# haasoscope_trigger_board_v1_1.net
KiCad netlist of a schematic drawn in EAGLE
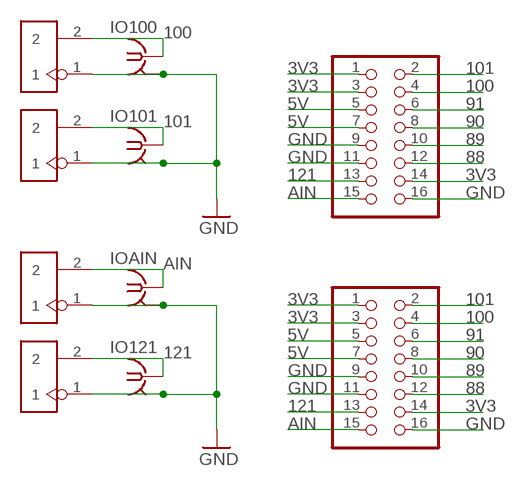
[diagram p0: schematic, sheet 1]

(export (version "E")
  (design (tool "Eeschema 10.0.6"))
  (components
    (comp (ref "IO100")
      (value "BU-SMB-V")
      (footprint "eagle-import:BU-SMB-V")
      (libsource (lib "eagle-import") (part "BU-SMB-V"))
    )
    (comp (ref "IO101")
      (value "BU-SMB-V")
      (footprint "eagle-import:BU-SMB-V")
      (libsource (lib "eagle-import") (part "BU-SMB-V"))
    )
    (comp (ref "IO121")
      (value "BU-SMB-V")
      (footprint "eagle-import:BU-SMB-V")
      (libsource (lib "eagle-import") (part "BU-SMB-V"))
    )
    (comp (ref "IOAIN")
      (value "BU-SMB-V")
      (footprint "eagle-import:BU-SMB-V")
      (libsource (lib "eagle-import") (part "BU-SMB-V"))
    )
    (comp (ref "J1")
      (value "2p-2.54")
      (footprint "eagle-import:H2-2.54")
      (fields (field (name "MPN") "P125-1102A0BS116A1"))
      (libsource (lib "eagle-import") (part "DIP-BLACK-MALE-HEADER-VERT(2P-2.54)"))
    )
    (comp (ref "J2")
      (value "2p-2.54")
      (footprint "eagle-import:H2-2.54")
      (fields (field (name "MPN") "P125-1102A0BS116A1"))
      (libsource (lib "eagle-import") (part "DIP-BLACK-MALE-HEADER-VERT(2P-2.54)"))
    )
    (comp (ref "J3")
      (value "2p-2.54")
      (footprint "eagle-import:H2-2.54")
      (fields (field (name "MPN") "P125-1102A0BS116A1"))
      (libsource (lib "eagle-import") (part "DIP-BLACK-MALE-HEADER-VERT(2P-2.54)"))
    )
    (comp (ref "J4")
      (value "2p-2.54")
      (footprint "eagle-import:H2-2.54")
      (fields (field (name "MPN") "P125-1102A0BS116A1"))
      (libsource (lib "eagle-import") (part "DIP-BLACK-MALE-HEADER-VERT(2P-2.54)"))
    )
    (comp (ref "JP1")
      (value "Jp1")
      (footprint "eagle-import:2X08")
      (libsource (lib "eagle-import") (part "PINHD-2X8"))
    )
    (comp (ref "JP2")
      (value "JP2")
      (footprint "eagle-import:2X08")
      (libsource (lib "eagle-import") (part "PINHD-2X8"))
    )
  )
  (nets
    (net (code "1") (name "/3V3") (class "Default")
      (node (ref "JP1") (pin "1") (pinfunction "1_1") (pintype "passive"))
      (node (ref "JP1") (pin "14") (pinfunction "14_14") (pintype "passive"))
      (node (ref "JP1") (pin "3") (pinfunction "3_3") (pintype "passive"))
      (node (ref "JP2") (pin "1") (pinfunction "1_1") (pintype "passive"))
      (node (ref "JP2") (pin "14") (pinfunction "14_14") (pintype "passive"))
      (node (ref "JP2") (pin "3") (pinfunction "3_3") (pintype "passive"))
    )
    (net (code "2") (name "/5V") (class "Default")
      (node (ref "JP1") (pin "5") (pinfunction "5_5") (pintype "passive"))
      (node (ref "JP1") (pin "7") (pinfunction "7_7") (pintype "passive"))
      (node (ref "JP2") (pin "5") (pinfunction "5_5") (pintype "passive"))
      (node (ref "JP2") (pin "7") (pinfunction "7_7") (pintype "passive"))
    )
    (net (code "3") (name "/88") (class "Default")
      (node (ref "JP1") (pin "12") (pinfunction "12_12") (pintype "passive"))
      (node (ref "JP2") (pin "12") (pinfunction "12_12") (pintype "passive"))
    )
    (net (code "4") (name "/89") (class "Default")
      (node (ref "JP1") (pin "10") (pinfunction "10_10") (pintype "passive"))
      (node (ref "JP2") (pin "10") (pinfunction "10_10") (pintype "passive"))
    )
    (net (code "5") (name "/90") (class "Default")
      (node (ref "JP1") (pin "8") (pinfunction "8_8") (pintype "passive"))
      (node (ref "JP2") (pin "8") (pinfunction "8_8") (pintype "passive"))
    )
    (net (code "6") (name "/91") (class "Default")
      (node (ref "JP1") (pin "6") (pinfunction "6_6") (pintype "passive"))
      (node (ref "JP2") (pin "6") (pinfunction "6_6") (pintype "passive"))
    )
    (net (code "7") (name "/100") (class "Default")
      (node (ref "IO100") (pin "1") (pinfunction "1_1") (pintype "passive"))
      (node (ref "J1") (pin "2") (pinfunction "2_2") (pintype "bidirectional"))
      (node (ref "JP1") (pin "4") (pinfunction "4_4") (pintype "passive"))
      (node (ref "JP2") (pin "4") (pinfunction "4_4") (pintype "passive"))
    )
    (net (code "8") (name "/101") (class "Default")
      (node (ref "IO101") (pin "1") (pinfunction "1_1") (pintype "passive"))
      (node (ref "J2") (pin "2") (pinfunction "2_2") (pintype "bidirectional"))
      (node (ref "JP1") (pin "2") (pinfunction "2_2") (pintype "passive"))
      (node (ref "JP2") (pin "2") (pinfunction "2_2") (pintype "passive"))
    )
    (net (code "9") (name "/121") (class "Default")
      (node (ref "IO121") (pin "1") (pinfunction "1_1") (pintype "passive"))
      (node (ref "J4") (pin "2") (pinfunction "2_2") (pintype "bidirectional"))
      (node (ref "JP1") (pin "13") (pinfunction "13_13") (pintype "passive"))
      (node (ref "JP2") (pin "13") (pinfunction "13_13") (pintype "passive"))
    )
    (net (code "10") (name "/AIN") (class "Default")
      (node (ref "IOAIN") (pin "1") (pinfunction "1_1") (pintype "passive"))
      (node (ref "J3") (pin "2") (pinfunction "2_2") (pintype "bidirectional"))
      (node (ref "JP1") (pin "15") (pinfunction "15_15") (pintype "passive"))
      (node (ref "JP2") (pin "15") (pinfunction "15_15") (pintype "passive"))
    )
    (net (code "11") (name "GND") (class "Default")
      (node (ref "IO100") (pin "2") (pinfunction "2_2") (pintype "passive"))
      (node (ref "IO100") (pin "3") (pinfunction "2_3") (pintype "passive"))
      (node (ref "IO100") (pin "4") (pinfunction "2_4") (pintype "passive"))
      (node (ref "IO100") (pin "5") (pinfunction "2_5") (pintype "passive"))
      (node (ref "IO101") (pin "2") (pinfunction "2_2") (pintype "passive"))
      (node (ref "IO101") (pin "3") (pinfunction "2_3") (pintype "passive"))
      (node (ref "IO101") (pin "4") (pinfunction "2_4") (pintype "passive"))
      (node (ref "IO101") (pin "5") (pinfunction "2_5") (pintype "passive"))
      (node (ref "IO121") (pin "2") (pinfunction "2_2") (pintype "passive"))
      (node (ref "IO121") (pin "3") (pinfunction "2_3") (pintype "passive"))
      (node (ref "IO121") (pin "4") (pinfunction "2_4") (pintype "passive"))
      (node (ref "IO121") (pin "5") (pinfunction "2_5") (pintype "passive"))
      (node (ref "IOAIN") (pin "2") (pinfunction "2_2") (pintype "passive"))
      (node (ref "IOAIN") (pin "3") (pinfunction "2_3") (pintype "passive"))
      (node (ref "IOAIN") (pin "4") (pinfunction "2_4") (pintype "passive"))
      (node (ref "IOAIN") (pin "5") (pinfunction "2_5") (pintype "passive"))
      (node (ref "J1") (pin "1") (pinfunction "1_1") (pintype "bidirectional"))
      (node (ref "J2") (pin "1") (pinfunction "1_1") (pintype "bidirectional"))
      (node (ref "J3") (pin "1") (pinfunction "1_1") (pintype "bidirectional"))
      (node (ref "J4") (pin "1") (pinfunction "1_1") (pintype "bidirectional"))
      (node (ref "JP1") (pin "11") (pinfunction "11_11") (pintype "passive"))
      (node (ref "JP1") (pin "16") (pinfunction "16_16") (pintype "passive"))
      (node (ref "JP1") (pin "9") (pinfunction "9_9") (pintype "passive"))
      (node (ref "JP2") (pin "11") (pinfunction "11_11") (pintype "passive"))
      (node (ref "JP2") (pin "16") (pinfunction "16_16") (pintype "passive"))
      (node (ref "JP2") (pin "9") (pinfunction "9_9") (pintype "passive"))
    )
  )
)
